# picotouch_grid.net
KiCad netlist of a schematic drawn in EAGLE
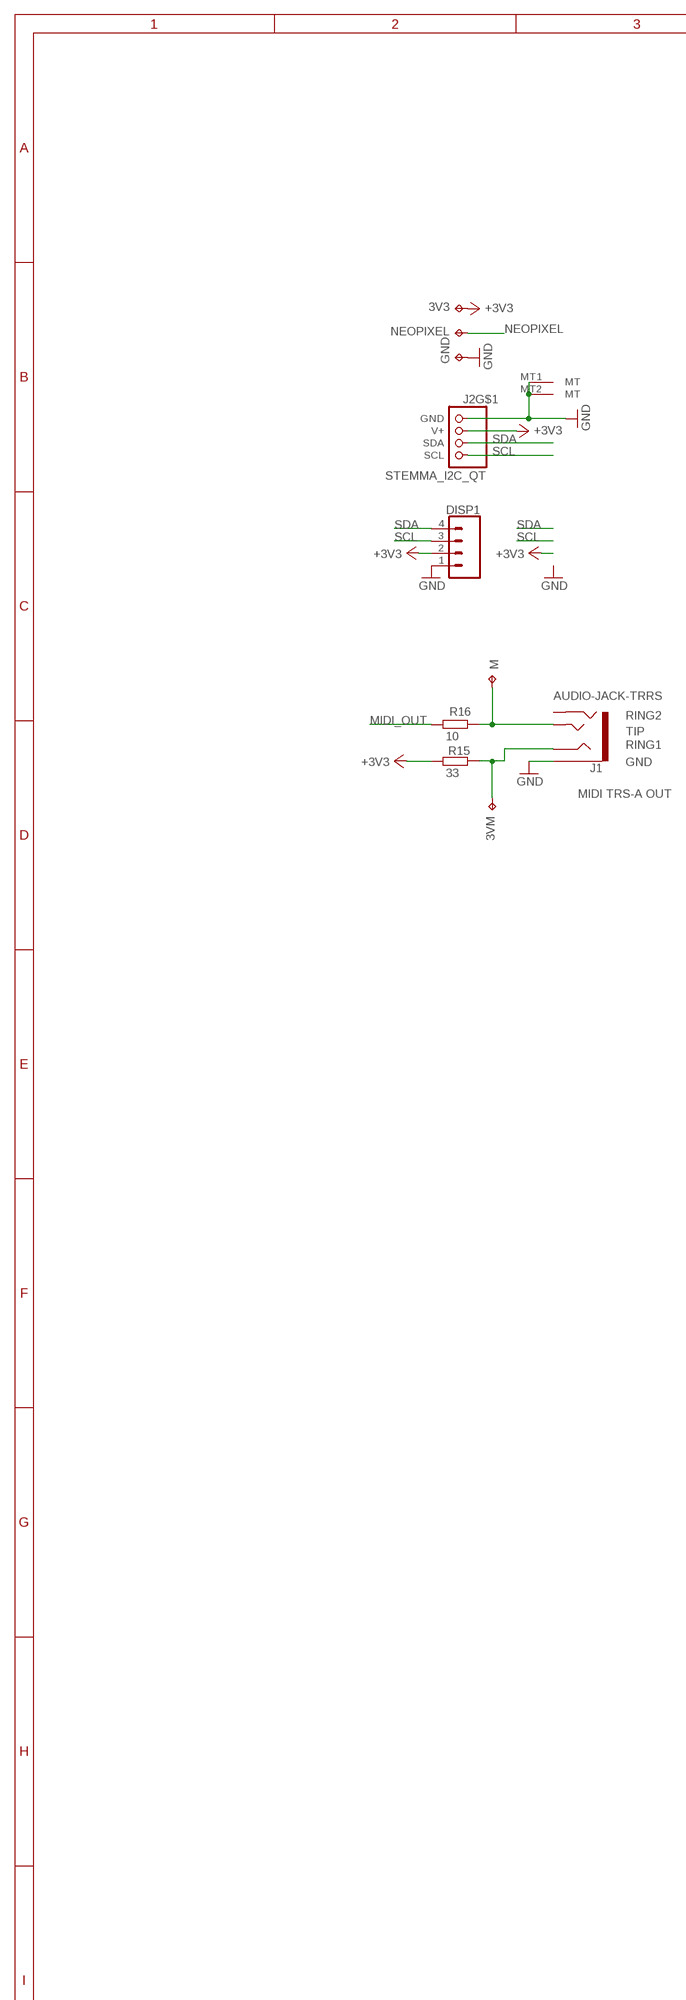
[diagram p0: schematic, sheet 1, part 1 of 2]
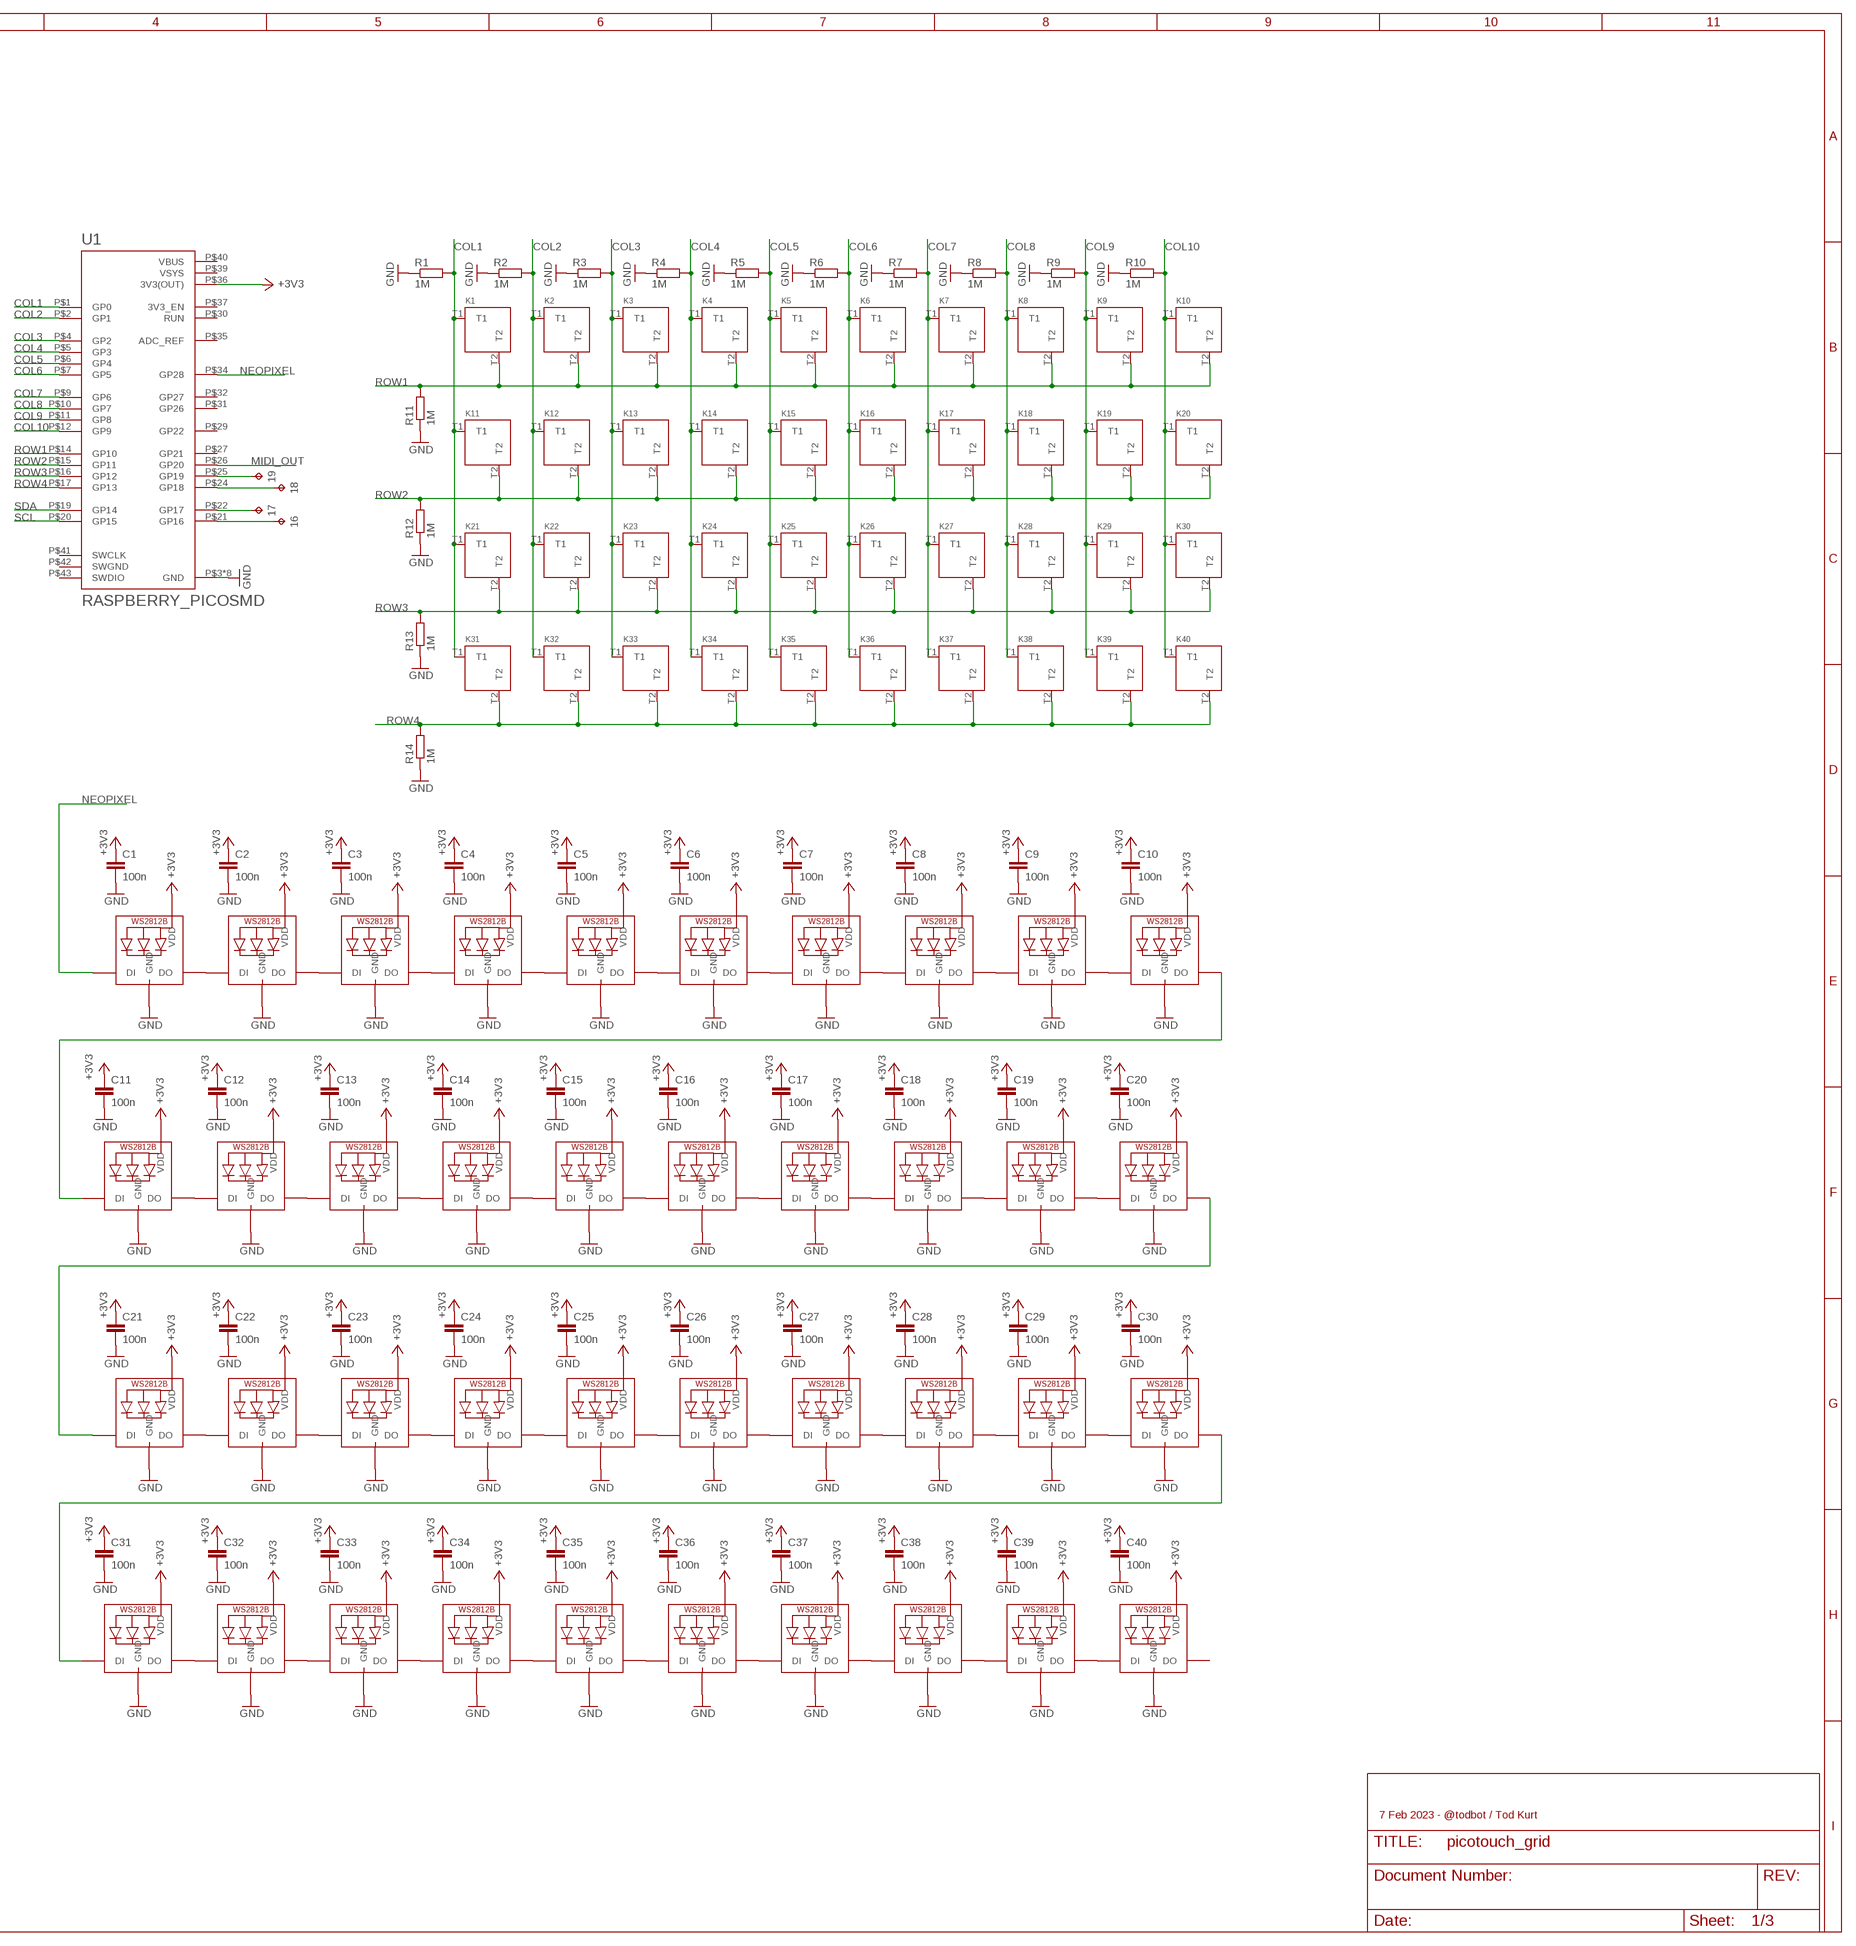
[diagram p1: schematic, sheet 1, part 2 of 2]

(export (version "E")
  (design (tool "Eeschema 10.0.6"))
  (components
    (comp (ref "3V3")
      (value "TPTP15R")
      (footprint "eagle-import:TP15R")
      (libsource (lib "eagle-import") (part "TPTP15R"))
    )
    (comp (ref "3VM")
      (value "TPTP15R")
      (footprint "eagle-import:TP15R")
      (libsource (lib "eagle-import") (part "TPTP15R"))
    )
    (comp (ref "16")
      (value "TPTP15R")
      (footprint "eagle-import:TP15R")
      (libsource (lib "eagle-import") (part "TPTP15R"))
    )
    (comp (ref "17")
      (value "TPTP15R")
      (footprint "eagle-import:TP15R")
      (libsource (lib "eagle-import") (part "TPTP15R"))
    )
    (comp (ref "18")
      (value "TPTP15R")
      (footprint "eagle-import:TP15R")
      (libsource (lib "eagle-import") (part "TPTP15R"))
    )
    (comp (ref "19")
      (value "TPTP15R")
      (footprint "eagle-import:TP15R")
      (libsource (lib "eagle-import") (part "TPTP15R"))
    )
    (comp (ref "C1")
      (value "100n")
      (footprint "eagle-import:C0805")
      (libsource (lib "eagle-import") (part "C-EUC0805"))
    )
    (comp (ref "C2")
      (value "100n")
      (footprint "eagle-import:C0805")
      (libsource (lib "eagle-import") (part "C-EUC0805"))
    )
    (comp (ref "C3")
      (value "100n")
      (footprint "eagle-import:C0805")
      (libsource (lib "eagle-import") (part "C-EUC0805"))
    )
    (comp (ref "C4")
      (value "100n")
      (footprint "eagle-import:C0805")
      (libsource (lib "eagle-import") (part "C-EUC0805"))
    )
    (comp (ref "C5")
      (value "100n")
      (footprint "eagle-import:C0805")
      (libsource (lib "eagle-import") (part "C-EUC0805"))
    )
    (comp (ref "C6")
      (value "100n")
      (footprint "eagle-import:C0805")
      (libsource (lib "eagle-import") (part "C-EUC0805"))
    )
    (comp (ref "C7")
      (value "100n")
      (footprint "eagle-import:C0805")
      (libsource (lib "eagle-import") (part "C-EUC0805"))
    )
    (comp (ref "C8")
      (value "100n")
      (footprint "eagle-import:C0805")
      (libsource (lib "eagle-import") (part "C-EUC0805"))
    )
    (comp (ref "C9")
      (value "100n")
      (footprint "eagle-import:C0805")
      (libsource (lib "eagle-import") (part "C-EUC0805"))
    )
    (comp (ref "C10")
      (value "100n")
      (footprint "eagle-import:C0805")
      (libsource (lib "eagle-import") (part "C-EUC0805"))
    )
    (comp (ref "C11")
      (value "100n")
      (footprint "eagle-import:C0805")
      (libsource (lib "eagle-import") (part "C-EUC0805"))
    )
    (comp (ref "C12")
      (value "100n")
      (footprint "eagle-import:C0805")
      (libsource (lib "eagle-import") (part "C-EUC0805"))
    )
    (comp (ref "C13")
      (value "100n")
      (footprint "eagle-import:C0805")
      (libsource (lib "eagle-import") (part "C-EUC0805"))
    )
    (comp (ref "C14")
      (value "100n")
      (footprint "eagle-import:C0805")
      (libsource (lib "eagle-import") (part "C-EUC0805"))
    )
    (comp (ref "C15")
      (value "100n")
      (footprint "eagle-import:C0805")
      (libsource (lib "eagle-import") (part "C-EUC0805"))
    )
    (comp (ref "C16")
      (value "100n")
      (footprint "eagle-import:C0805")
      (libsource (lib "eagle-import") (part "C-EUC0805"))
    )
    (comp (ref "C17")
      (value "100n")
      (footprint "eagle-import:C0805")
      (libsource (lib "eagle-import") (part "C-EUC0805"))
    )
    (comp (ref "C18")
      (value "100n")
      (footprint "eagle-import:C0805")
      (libsource (lib "eagle-import") (part "C-EUC0805"))
    )
    (comp (ref "C19")
      (value "100n")
      (footprint "eagle-import:C0805")
      (libsource (lib "eagle-import") (part "C-EUC0805"))
    )
    (comp (ref "C20")
      (value "100n")
      (footprint "eagle-import:C0805")
      (libsource (lib "eagle-import") (part "C-EUC0805"))
    )
    (comp (ref "C21")
      (value "100n")
      (footprint "eagle-import:C0805")
      (libsource (lib "eagle-import") (part "C-EUC0805"))
    )
    (comp (ref "C22")
      (value "100n")
      (footprint "eagle-import:C0805")
      (libsource (lib "eagle-import") (part "C-EUC0805"))
    )
    (comp (ref "C23")
      (value "100n")
      (footprint "eagle-import:C0805")
      (libsource (lib "eagle-import") (part "C-EUC0805"))
    )
    (comp (ref "C24")
      (value "100n")
      (footprint "eagle-import:C0805")
      (libsource (lib "eagle-import") (part "C-EUC0805"))
    )
    (comp (ref "C25")
      (value "100n")
      (footprint "eagle-import:C0805")
      (libsource (lib "eagle-import") (part "C-EUC0805"))
    )
    (comp (ref "C26")
      (value "100n")
      (footprint "eagle-import:C0805")
      (libsource (lib "eagle-import") (part "C-EUC0805"))
    )
    (comp (ref "C27")
      (value "100n")
      (footprint "eagle-import:C0805")
      (libsource (lib "eagle-import") (part "C-EUC0805"))
    )
    (comp (ref "C28")
      (value "100n")
      (footprint "eagle-import:C0805")
      (libsource (lib "eagle-import") (part "C-EUC0805"))
    )
    (comp (ref "C29")
      (value "100n")
      (footprint "eagle-import:C0805")
      (libsource (lib "eagle-import") (part "C-EUC0805"))
    )
    (comp (ref "C30")
      (value "100n")
      (footprint "eagle-import:C0805")
      (libsource (lib "eagle-import") (part "C-EUC0805"))
    )
    (comp (ref "C31")
      (value "100n")
      (footprint "eagle-import:C0805")
      (libsource (lib "eagle-import") (part "C-EUC0805"))
    )
    (comp (ref "C32")
      (value "100n")
      (footprint "eagle-import:C0805")
      (libsource (lib "eagle-import") (part "C-EUC0805"))
    )
    (comp (ref "C33")
      (value "100n")
      (footprint "eagle-import:C0805")
      (libsource (lib "eagle-import") (part "C-EUC0805"))
    )
    (comp (ref "C34")
      (value "100n")
      (footprint "eagle-import:C0805")
      (libsource (lib "eagle-import") (part "C-EUC0805"))
    )
    (comp (ref "C35")
      (value "100n")
      (footprint "eagle-import:C0805")
      (libsource (lib "eagle-import") (part "C-EUC0805"))
    )
    (comp (ref "C36")
      (value "100n")
      (footprint "eagle-import:C0805")
      (libsource (lib "eagle-import") (part "C-EUC0805"))
    )
    (comp (ref "C37")
      (value "100n")
      (footprint "eagle-import:C0805")
      (libsource (lib "eagle-import") (part "C-EUC0805"))
    )
    (comp (ref "C38")
      (value "100n")
      (footprint "eagle-import:C0805")
      (libsource (lib "eagle-import") (part "C-EUC0805"))
    )
    (comp (ref "C39")
      (value "100n")
      (footprint "eagle-import:C0805")
      (libsource (lib "eagle-import") (part "C-EUC0805"))
    )
    (comp (ref "C40")
      (value "100n")
      (footprint "eagle-import:C0805")
      (libsource (lib "eagle-import") (part "C-EUC0805"))
    )
    (comp (ref "DISP1")
      (value "CONN_04")
      (footprint "eagle-import:1X04")
      (libsource (lib "eagle-import") (part "CONN_04"))
    )
    (comp (ref "GND")
      (value "TPTP15R")
      (footprint "eagle-import:TP15R")
      (libsource (lib "eagle-import") (part "TPTP15R"))
    )
    (comp (ref "J1")
      (value "AUDIO-JACK-TRRS")
      (footprint "eagle-import:PJ-320D_SPARKFUN")
      (fields (field (name "MPN") "PJ-320D") (field (name "LCSC") "C431535"))
      (libsource (lib "eagle-import") (part "AUDIO-JACK-TRRS"))
    )
    (comp (ref "J2")
      (value "STEMMA_I2C_QT")
      (footprint "eagle-import:JST_SH4")
      (fields
        (field (name "MPN") "HC-1.0-4PWT")
        (field (name "LCSC2") "C160404")
        (field (name "MPN2") "SM04B-SRSS-TB")
      )
      (libsource (lib "eagle-import") (part "STEMMA_I2C_QT"))
    )
    (comp (ref "K1")
      (value "TOUCHKEYH")
      (footprint "eagle-import:TOUCHPAD_KEY_0.5IN_LEDHOLE")
      (libsource (lib "eagle-import") (part "TOUCHKEYH"))
    )
    (comp (ref "K2")
      (value "TOUCHKEYH")
      (footprint "eagle-import:TOUCHPAD_KEY_0.5IN_LEDHOLE")
      (libsource (lib "eagle-import") (part "TOUCHKEYH"))
    )
    (comp (ref "K3")
      (value "TOUCHKEYH")
      (footprint "eagle-import:TOUCHPAD_KEY_0.5IN_LEDHOLE")
      (libsource (lib "eagle-import") (part "TOUCHKEYH"))
    )
    (comp (ref "K4")
      (value "TOUCHKEYH")
      (footprint "eagle-import:TOUCHPAD_KEY_0.5IN_LEDHOLE")
      (libsource (lib "eagle-import") (part "TOUCHKEYH"))
    )
    (comp (ref "K5")
      (value "TOUCHKEYH")
      (footprint "eagle-import:TOUCHPAD_KEY_0.5IN_LEDHOLE")
      (libsource (lib "eagle-import") (part "TOUCHKEYH"))
    )
    (comp (ref "K6")
      (value "TOUCHKEYH")
      (footprint "eagle-import:TOUCHPAD_KEY_0.5IN_LEDHOLE")
      (libsource (lib "eagle-import") (part "TOUCHKEYH"))
    )
    (comp (ref "K7")
      (value "TOUCHKEYH")
      (footprint "eagle-import:TOUCHPAD_KEY_0.5IN_LEDHOLE")
      (libsource (lib "eagle-import") (part "TOUCHKEYH"))
    )
    (comp (ref "K8")
      (value "TOUCHKEYH")
      (footprint "eagle-import:TOUCHPAD_KEY_0.5IN_LEDHOLE")
      (libsource (lib "eagle-import") (part "TOUCHKEYH"))
    )
    (comp (ref "K9")
      (value "TOUCHKEYH")
      (footprint "eagle-import:TOUCHPAD_KEY_0.5IN_LEDHOLE")
      (libsource (lib "eagle-import") (part "TOUCHKEYH"))
    )
    (comp (ref "K10")
      (value "TOUCHKEYH")
      (footprint "eagle-import:TOUCHPAD_KEY_0.5IN_LEDHOLE")
      (libsource (lib "eagle-import") (part "TOUCHKEYH"))
    )
    (comp (ref "K11")
      (value "TOUCHKEYH")
      (footprint "eagle-import:TOUCHPAD_KEY_0.5IN_LEDHOLE")
      (libsource (lib "eagle-import") (part "TOUCHKEYH"))
    )
    (comp (ref "K12")
      (value "TOUCHKEYH")
      (footprint "eagle-import:TOUCHPAD_KEY_0.5IN_LEDHOLE")
      (libsource (lib "eagle-import") (part "TOUCHKEYH"))
    )
    (comp (ref "K13")
      (value "TOUCHKEYH")
      (footprint "eagle-import:TOUCHPAD_KEY_0.5IN_LEDHOLE")
      (libsource (lib "eagle-import") (part "TOUCHKEYH"))
    )
    (comp (ref "K14")
      (value "TOUCHKEYH")
      (footprint "eagle-import:TOUCHPAD_KEY_0.5IN_LEDHOLE")
      (libsource (lib "eagle-import") (part "TOUCHKEYH"))
    )
    (comp (ref "K15")
      (value "TOUCHKEYH")
      (footprint "eagle-import:TOUCHPAD_KEY_0.5IN_LEDHOLE")
      (libsource (lib "eagle-import") (part "TOUCHKEYH"))
    )
    (comp (ref "K16")
      (value "TOUCHKEYH")
      (footprint "eagle-import:TOUCHPAD_KEY_0.5IN_LEDHOLE")
      (libsource (lib "eagle-import") (part "TOUCHKEYH"))
    )
    (comp (ref "K17")
      (value "TOUCHKEYH")
      (footprint "eagle-import:TOUCHPAD_KEY_0.5IN_LEDHOLE")
      (libsource (lib "eagle-import") (part "TOUCHKEYH"))
    )
    (comp (ref "K18")
      (value "TOUCHKEYH")
      (footprint "eagle-import:TOUCHPAD_KEY_0.5IN_LEDHOLE")
      (libsource (lib "eagle-import") (part "TOUCHKEYH"))
    )
    (comp (ref "K19")
      (value "TOUCHKEYH")
      (footprint "eagle-import:TOUCHPAD_KEY_0.5IN_LEDHOLE")
      (libsource (lib "eagle-import") (part "TOUCHKEYH"))
    )
    (comp (ref "K20")
      (value "TOUCHKEYH")
      (footprint "eagle-import:TOUCHPAD_KEY_0.5IN_LEDHOLE")
      (libsource (lib "eagle-import") (part "TOUCHKEYH"))
    )
    (comp (ref "K21")
      (value "TOUCHKEYH")
      (footprint "eagle-import:TOUCHPAD_KEY_0.5IN_LEDHOLE")
      (libsource (lib "eagle-import") (part "TOUCHKEYH"))
    )
    (comp (ref "K22")
      (value "TOUCHKEYH")
      (footprint "eagle-import:TOUCHPAD_KEY_0.5IN_LEDHOLE")
      (libsource (lib "eagle-import") (part "TOUCHKEYH"))
    )
    (comp (ref "K23")
      (value "TOUCHKEYH")
      (footprint "eagle-import:TOUCHPAD_KEY_0.5IN_LEDHOLE")
      (libsource (lib "eagle-import") (part "TOUCHKEYH"))
    )
    (comp (ref "K24")
      (value "TOUCHKEYH")
      (footprint "eagle-import:TOUCHPAD_KEY_0.5IN_LEDHOLE")
      (libsource (lib "eagle-import") (part "TOUCHKEYH"))
    )
    (comp (ref "K25")
      (value "TOUCHKEYH")
      (footprint "eagle-import:TOUCHPAD_KEY_0.5IN_LEDHOLE")
      (libsource (lib "eagle-import") (part "TOUCHKEYH"))
    )
    (comp (ref "K26")
      (value "TOUCHKEYH")
      (footprint "eagle-import:TOUCHPAD_KEY_0.5IN_LEDHOLE")
      (libsource (lib "eagle-import") (part "TOUCHKEYH"))
    )
    (comp (ref "K27")
      (value "TOUCHKEYH")
      (footprint "eagle-import:TOUCHPAD_KEY_0.5IN_LEDHOLE")
      (libsource (lib "eagle-import") (part "TOUCHKEYH"))
    )
    (comp (ref "K28")
      (value "TOUCHKEYH")
      (footprint "eagle-import:TOUCHPAD_KEY_0.5IN_LEDHOLE")
      (libsource (lib "eagle-import") (part "TOUCHKEYH"))
    )
    (comp (ref "K29")
      (value "TOUCHKEYH")
      (footprint "eagle-import:TOUCHPAD_KEY_0.5IN_LEDHOLE")
      (libsource (lib "eagle-import") (part "TOUCHKEYH"))
    )
    (comp (ref "K30")
      (value "TOUCHKEYH")
      (footprint "eagle-import:TOUCHPAD_KEY_0.5IN_LEDHOLE")
      (libsource (lib "eagle-import") (part "TOUCHKEYH"))
    )
    (comp (ref "K31")
      (value "TOUCHKEYH")
      (footprint "eagle-import:TOUCHPAD_KEY_0.5IN_LEDHOLE")
      (libsource (lib "eagle-import") (part "TOUCHKEYH"))
    )
    (comp (ref "K32")
      (value "TOUCHKEYH")
      (footprint "eagle-import:TOUCHPAD_KEY_0.5IN_LEDHOLE")
      (libsource (lib "eagle-import") (part "TOUCHKEYH"))
    )
    (comp (ref "K33")
      (value "TOUCHKEYH")
      (footprint "eagle-import:TOUCHPAD_KEY_0.5IN_LEDHOLE")
      (libsource (lib "eagle-import") (part "TOUCHKEYH"))
    )
    (comp (ref "K34")
      (value "TOUCHKEYH")
      (footprint "eagle-import:TOUCHPAD_KEY_0.5IN_LEDHOLE")
      (libsource (lib "eagle-import") (part "TOUCHKEYH"))
    )
    (comp (ref "K35")
      (value "TOUCHKEYH")
      (footprint "eagle-import:TOUCHPAD_KEY_0.5IN_LEDHOLE")
      (libsource (lib "eagle-import") (part "TOUCHKEYH"))
    )
    (comp (ref "K36")
      (value "TOUCHKEYH")
      (footprint "eagle-import:TOUCHPAD_KEY_0.5IN_LEDHOLE")
      (libsource (lib "eagle-import") (part "TOUCHKEYH"))
    )
    (comp (ref "K37")
      (value "TOUCHKEYH")
      (footprint "eagle-import:TOUCHPAD_KEY_0.5IN_LEDHOLE")
      (libsource (lib "eagle-import") (part "TOUCHKEYH"))
    )
    (comp (ref "K38")
      (value "TOUCHKEYH")
      (footprint "eagle-import:TOUCHPAD_KEY_0.5IN_LEDHOLE")
      (libsource (lib "eagle-import") (part "TOUCHKEYH"))
    )
    (comp (ref "K39")
      (value "TOUCHKEYH")
      (footprint "eagle-import:TOUCHPAD_KEY_0.5IN_LEDHOLE")
      (libsource (lib "eagle-import") (part "TOUCHKEYH"))
    )
    (comp (ref "K40")
      (value "TOUCHKEYH")
      (footprint "eagle-import:TOUCHPAD_KEY_0.5IN_LEDHOLE")
      (libsource (lib "eagle-import") (part "TOUCHKEYH"))
    )
    (comp (ref "LED1")
      (value "MICROBUILDER_WS2812B_SK6812E")
      (footprint "eagle-import:MICROBUILDER_NEO3535_REVERSE")
      (libsource (lib "eagle-import") (part "MICROBUILDER_WS2812B_SK6812E"))
    )
    (comp (ref "LED2")
      (value "MICROBUILDER_WS2812B_SK6812E")
      (footprint "eagle-import:MICROBUILDER_NEO3535_REVERSE")
      (libsource (lib "eagle-import") (part "MICROBUILDER_WS2812B_SK6812E"))
    )
    (comp (ref "LED3")
      (value "MICROBUILDER_WS2812B_SK6812E")
      (footprint "eagle-import:MICROBUILDER_NEO3535_REVERSE")
      (libsource (lib "eagle-import") (part "MICROBUILDER_WS2812B_SK6812E"))
    )
    (comp (ref "LED4")
      (value "MICROBUILDER_WS2812B_SK6812E")
      (footprint "eagle-import:MICROBUILDER_NEO3535_REVERSE")
      (libsource (lib "eagle-import") (part "MICROBUILDER_WS2812B_SK6812E"))
    )
    (comp (ref "LED5")
      (value "MICROBUILDER_WS2812B_SK6812E")
      (footprint "eagle-import:MICROBUILDER_NEO3535_REVERSE")
      (libsource (lib "eagle-import") (part "MICROBUILDER_WS2812B_SK6812E"))
    )
    (comp (ref "LED6")
      (value "MICROBUILDER_WS2812B_SK6812E")
      (footprint "eagle-import:MICROBUILDER_NEO3535_REVERSE")
      (libsource (lib "eagle-import") (part "MICROBUILDER_WS2812B_SK6812E"))
    )
    (comp (ref "LED7")
      (value "MICROBUILDER_WS2812B_SK6812E")
      (footprint "eagle-import:MICROBUILDER_NEO3535_REVERSE")
      (libsource (lib "eagle-import") (part "MICROBUILDER_WS2812B_SK6812E"))
    )
    (comp (ref "LED8")
      (value "MICROBUILDER_WS2812B_SK6812E")
      (footprint "eagle-import:MICROBUILDER_NEO3535_REVERSE")
      (libsource (lib "eagle-import") (part "MICROBUILDER_WS2812B_SK6812E"))
    )
    (comp (ref "LED9")
      (value "MICROBUILDER_WS2812B_SK6812E")
      (footprint "eagle-import:MICROBUILDER_NEO3535_REVERSE")
      (libsource (lib "eagle-import") (part "MICROBUILDER_WS2812B_SK6812E"))
    )
    (comp (ref "LED10")
      (value "MICROBUILDER_WS2812B_SK6812E")
      (footprint "eagle-import:MICROBUILDER_NEO3535_REVERSE")
      (libsource (lib "eagle-import") (part "MICROBUILDER_WS2812B_SK6812E"))
    )
    (comp (ref "LED11")
      (value "MICROBUILDER_WS2812B_SK6812E")
      (footprint "eagle-import:MICROBUILDER_NEO3535_REVERSE")
      (libsource (lib "eagle-import") (part "MICROBUILDER_WS2812B_SK6812E"))
    )
    (comp (ref "LED12")
      (value "MICROBUILDER_WS2812B_SK6812E")
      (footprint "eagle-import:MICROBUILDER_NEO3535_REVERSE")
      (libsource (lib "eagle-import") (part "MICROBUILDER_WS2812B_SK6812E"))
    )
    (comp (ref "LED13")
      (value "MICROBUILDER_WS2812B_SK6812E")
      (footprint "eagle-import:MICROBUILDER_NEO3535_REVERSE")
      (libsource (lib "eagle-import") (part "MICROBUILDER_WS2812B_SK6812E"))
    )
    (comp (ref "LED14")
      (value "MICROBUILDER_WS2812B_SK6812E")
      (footprint "eagle-import:MICROBUILDER_NEO3535_REVERSE")
      (libsource (lib "eagle-import") (part "MICROBUILDER_WS2812B_SK6812E"))
    )
    (comp (ref "LED15")
      (value "MICROBUILDER_WS2812B_SK6812E")
      (footprint "eagle-import:MICROBUILDER_NEO3535_REVERSE")
      (libsource (lib "eagle-import") (part "MICROBUILDER_WS2812B_SK6812E"))
    )
    (comp (ref "LED16")
      (value "MICROBUILDER_WS2812B_SK6812E")
      (footprint "eagle-import:MICROBUILDER_NEO3535_REVERSE")
      (libsource (lib "eagle-import") (part "MICROBUILDER_WS2812B_SK6812E"))
    )
    (comp (ref "LED17")
      (value "MICROBUILDER_WS2812B_SK6812E")
      (footprint "eagle-import:MICROBUILDER_NEO3535_REVERSE")
      (libsource (lib "eagle-import") (part "MICROBUILDER_WS2812B_SK6812E"))
    )
    (comp (ref "LED18")
      (value "MICROBUILDER_WS2812B_SK6812E")
      (footprint "eagle-import:MICROBUILDER_NEO3535_REVERSE")
      (libsource (lib "eagle-import") (part "MICROBUILDER_WS2812B_SK6812E"))
    )
    (comp (ref "LED19")
      (value "MICROBUILDER_WS2812B_SK6812E")
      (footprint "eagle-import:MICROBUILDER_NEO3535_REVERSE")
      (libsource (lib "eagle-import") (part "MICROBUILDER_WS2812B_SK6812E"))
    )
    (comp (ref "LED20")
      (value "MICROBUILDER_WS2812B_SK6812E")
      (footprint "eagle-import:MICROBUILDER_NEO3535_REVERSE")
      (libsource (lib "eagle-import") (part "MICROBUILDER_WS2812B_SK6812E"))
    )
    (comp (ref "LED21")
      (value "MICROBUILDER_WS2812B_SK6812E")
      (footprint "eagle-import:MICROBUILDER_NEO3535_REVERSE")
      (libsource (lib "eagle-import") (part "MICROBUILDER_WS2812B_SK6812E"))
    )
    (comp (ref "LED22")
      (value "MICROBUILDER_WS2812B_SK6812E")
      (footprint "eagle-import:MICROBUILDER_NEO3535_REVERSE")
      (libsource (lib "eagle-import") (part "MICROBUILDER_WS2812B_SK6812E"))
    )
    (comp (ref "LED23")
      (value "MICROBUILDER_WS2812B_SK6812E")
      (footprint "eagle-import:MICROBUILDER_NEO3535_REVERSE")
      (libsource (lib "eagle-import") (part "MICROBUILDER_WS2812B_SK6812E"))
    )
    (comp (ref "LED24")
      (value "MICROBUILDER_WS2812B_SK6812E")
      (footprint "eagle-import:MICROBUILDER_NEO3535_REVERSE")
      (libsource (lib "eagle-import") (part "MICROBUILDER_WS2812B_SK6812E"))
    )
    (comp (ref "LED25")
      (value "MICROBUILDER_WS2812B_SK6812E")
      (footprint "eagle-import:MICROBUILDER_NEO3535_REVERSE")
      (libsource (lib "eagle-import") (part "MICROBUILDER_WS2812B_SK6812E"))
    )
    (comp (ref "LED26")
      (value "MICROBUILDER_WS2812B_SK6812E")
      (footprint "eagle-import:MICROBUILDER_NEO3535_REVERSE")
      (libsource (lib "eagle-import") (part "MICROBUILDER_WS2812B_SK6812E"))
    )
    (comp (ref "LED27")
      (value "MICROBUILDER_WS2812B_SK6812E")
      (footprint "eagle-import:MICROBUILDER_NEO3535_REVERSE")
      (libsource (lib "eagle-import") (part "MICROBUILDER_WS2812B_SK6812E"))
    )
    (comp (ref "LED28")
      (value "MICROBUILDER_WS2812B_SK6812E")
      (footprint "eagle-import:MICROBUILDER_NEO3535_REVERSE")
      (libsource (lib "eagle-import") (part "MICROBUILDER_WS2812B_SK6812E"))
    )
    (comp (ref "LED29")
      (value "MICROBUILDER_WS2812B_SK6812E")
      (footprint "eagle-import:MICROBUILDER_NEO3535_REVERSE")
      (libsource (lib "eagle-import") (part "MICROBUILDER_WS2812B_SK6812E"))
    )
    (comp (ref "LED30")
      (value "MICROBUILDER_WS2812B_SK6812E")
      (footprint "eagle-import:MICROBUILDER_NEO3535_REVERSE")
      (libsource (lib "eagle-import") (part "MICROBUILDER_WS2812B_SK6812E"))
    )
    (comp (ref "LED31")
      (value "MICROBUILDER_WS2812B_SK6812E")
      (footprint "eagle-import:MICROBUILDER_NEO3535_REVERSE")
      (libsource (lib "eagle-import") (part "MICROBUILDER_WS2812B_SK6812E"))
    )
    (comp (ref "LED32")
      (value "MICROBUILDER_WS2812B_SK6812E")
      (footprint "eagle-import:MICROBUILDER_NEO3535_REVERSE")
      (libsource (lib "eagle-import") (part "MICROBUILDER_WS2812B_SK6812E"))
    )
    (comp (ref "LED33")
      (value "MICROBUILDER_WS2812B_SK6812E")
      (footprint "eagle-import:MICROBUILDER_NEO3535_REVERSE")
      (libsource (lib "eagle-import") (part "MICROBUILDER_WS2812B_SK6812E"))
    )
    (comp (ref "LED34")
      (value "MICROBUILDER_WS2812B_SK6812E")
      (footprint "eagle-import:MICROBUILDER_NEO3535_REVERSE")
      (libsource (lib "eagle-import") (part "MICROBUILDER_WS2812B_SK6812E"))
    )
    (comp (ref "LED35")
      (value "MICROBUILDER_WS2812B_SK6812E")
      (footprint "eagle-import:MICROBUILDER_NEO3535_REVERSE")
      (libsource (lib "eagle-import") (part "MICROBUILDER_WS2812B_SK6812E"))
    )
    (comp (ref "LED36")
      (value "MICROBUILDER_WS2812B_SK6812E")
      (footprint "eagle-import:MICROBUILDER_NEO3535_REVERSE")
      (libsource (lib "eagle-import") (part "MICROBUILDER_WS2812B_SK6812E"))
    )
    (comp (ref "LED37")
      (value "MICROBUILDER_WS2812B_SK6812E")
      (footprint "eagle-import:MICROBUILDER_NEO3535_REVERSE")
      (libsource (lib "eagle-import") (part "MICROBUILDER_WS2812B_SK6812E"))
    )
    (comp (ref "LED38")
      (value "MICROBUILDER_WS2812B_SK6812E")
      (footprint "eagle-import:MICROBUILDER_NEO3535_REVERSE")
      (libsource (lib "eagle-import") (part "MICROBUILDER_WS2812B_SK6812E"))
    )
    (comp (ref "LED39")
      (value "MICROBUILDER_WS2812B_SK6812E")
      (footprint "eagle-import:MICROBUILDER_NEO3535_REVERSE")
      (libsource (lib "eagle-import") (part "MICROBUILDER_WS2812B_SK6812E"))
    )
    (comp (ref "LED40")
      (value "MICROBUILDER_WS2812B_SK6812E")
      (footprint "eagle-import:MICROBUILDER_NEO3535_REVERSE")
      (libsource (lib "eagle-import") (part "MICROBUILDER_WS2812B_SK6812E"))
    )
    (comp (ref "M")
      (value "TPTP15R")
      (footprint "eagle-import:TP15R")
      (libsource (lib "eagle-import") (part "TPTP15R"))
    )
    (comp (ref "NEOPIXEL")
      (value "TPTP15R")
      (footprint "eagle-import:TP15R")
      (libsource (lib "eagle-import") (part "TPTP15R"))
    )
    (comp (ref "R1")
      (value "1M")
      (footprint "eagle-import:R0805")
      (libsource (lib "eagle-import") (part "R-EU_R0805"))
    )
    (comp (ref "R2")
      (value "1M")
      (footprint "eagle-import:R0805")
      (libsource (lib "eagle-import") (part "R-EU_R0805"))
    )
    (comp (ref "R3")
      (value "1M")
      (footprint "eagle-import:R0805")
      (libsource (lib "eagle-import") (part "R-EU_R0805"))
    )
    (comp (ref "R4")
      (value "1M")
      (footprint "eagle-import:R0805")
      (libsource (lib "eagle-import") (part "R-EU_R0805"))
    )
    (comp (ref "R5")
      (value "1M")
      (footprint "eagle-import:R0805")
      (libsource (lib "eagle-import") (part "R-EU_R0805"))
    )
    (comp (ref "R6")
      (value "1M")
      (footprint "eagle-import:R0805")
      (libsource (lib "eagle-import") (part "R-EU_R0805"))
    )
    (comp (ref "R7")
      (value "1M")
      (footprint "eagle-import:R0805")
      (libsource (lib "eagle-import") (part "R-EU_R0805"))
    )
    (comp (ref "R8")
      (value "1M")
      (footprint "eagle-import:R0805")
      (libsource (lib "eagle-import") (part "R-EU_R0805"))
    )
    (comp (ref "R9")
      (value "1M")
      (footprint "eagle-import:R0805")
      (libsource (lib "eagle-import") (part "R-EU_R0805"))
    )
    (comp (ref "R10")
      (value "1M")
      (footprint "eagle-import:R0805")
      (libsource (lib "eagle-import") (part "R-EU_R0805"))
    )
    (comp (ref "R11")
      (value "1M")
      (footprint "eagle-import:R0805")
      (libsource (lib "eagle-import") (part "R-EU_R0805"))
    )
    (comp (ref "R12")
      (value "1M")
      (footprint "eagle-import:R0805")
      (libsource (lib "eagle-import") (part "R-EU_R0805"))
    )
    (comp (ref "R13")
      (value "1M")
      (footprint "eagle-import:R0805")
      (libsource (lib "eagle-import") (part "R-EU_R0805"))
    )
    (comp (ref "R14")
      (value "1M")
      (footprint "eagle-import:R0805")
      (libsource (lib "eagle-import") (part "R-EU_R0805"))
    )
    (comp (ref "R15")
      (value "33")
      (footprint "eagle-import:R0805")
      (libsource (lib "eagle-import") (part "R-EU_R0805"))
    )
    (comp (ref "R16")
      (value "10")
      (footprint "eagle-import:R0805")
      (libsource (lib "eagle-import") (part "R-EU_R0805"))
    )
    (comp (ref "U1")
      (value "RASPBERRY_PICOSMD")
      (footprint "eagle-import:PICO-PKG-SMD")
      (libsource (lib "eagle-import") (part "RASPBERRY_PICOSMD"))
    )
  )
  (nets
    (net (code "1") (name "+3V3") (class "Default")
      (node (ref "3V3") (pin "TP") (pinfunction "TP_TP") (pintype "input"))
      (node (ref "C1") (pin "1") (pinfunction "1_1") (pintype "passive"))
      (node (ref "C10") (pin "1") (pinfunction "1_1") (pintype "passive"))
      (node (ref "C11") (pin "1") (pinfunction "1_1") (pintype "passive"))
      (node (ref "C12") (pin "1") (pinfunction "1_1") (pintype "passive"))
      (node (ref "C13") (pin "1") (pinfunction "1_1") (pintype "passive"))
      (node (ref "C14") (pin "1") (pinfunction "1_1") (pintype "passive"))
      (node (ref "C15") (pin "1") (pinfunction "1_1") (pintype "passive"))
      (node (ref "C16") (pin "1") (pinfunction "1_1") (pintype "passive"))
      (node (ref "C17") (pin "1") (pinfunction "1_1") (pintype "passive"))
      (node (ref "C18") (pin "1") (pinfunction "1_1") (pintype "passive"))
      (node (ref "C19") (pin "1") (pinfunction "1_1") (pintype "passive"))
      (node (ref "C2") (pin "1") (pinfunction "1_1") (pintype "passive"))
      (node (ref "C20") (pin "1") (pinfunction "1_1") (pintype "passive"))
      (node (ref "C21") (pin "1") (pinfunction "1_1") (pintype "passive"))
      (node (ref "C22") (pin "1") (pinfunction "1_1") (pintype "passive"))
      (node (ref "C23") (pin "1") (pinfunction "1_1") (pintype "passive"))
      (node (ref "C24") (pin "1") (pinfunction "1_1") (pintype "passive"))
      (node (ref "C25") (pin "1") (pinfunction "1_1") (pintype "passive"))
      (node (ref "C26") (pin "1") (pinfunction "1_1") (pintype "passive"))
      (node (ref "C27") (pin "1") (pinfunction "1_1") (pintype "passive"))
      (node (ref "C28") (pin "1") (pinfunction "1_1") (pintype "passive"))
      (node (ref "C29") (pin "1") (pinfunction "1_1") (pintype "passive"))
      (node (ref "C3") (pin "1") (pinfunction "1_1") (pintype "passive"))
      (node (ref "C30") (pin "1") (pinfunction "1_1") (pintype "passive"))
      (node (ref "C31") (pin "1") (pinfunction "1_1") (pintype "passive"))
      (node (ref "C32") (pin "1") (pinfunction "1_1") (pintype "passive"))
      (node (ref "C33") (pin "1") (pinfunction "1_1") (pintype "passive"))
      (node (ref "C34") (pin "1") (pinfunction "1_1") (pintype "passive"))
      (node (ref "C35") (pin "1") (pinfunction "1_1") (pintype "passive"))
      (node (ref "C36") (pin "1") (pinfunction "1_1") (pintype "passive"))
      (node (ref "C37") (pin "1") (pinfunction "1_1") (pintype "passive"))
      (node (ref "C38") (pin "1") (pinfunction "1_1") (pintype "passive"))
      (node (ref "C39") (pin "1") (pinfunction "1_1") (pintype "passive"))
      (node (ref "C4") (pin "1") (pinfunction "1_1") (pintype "passive"))
      (node (ref "C40") (pin "1") (pinfunction "1_1") (pintype "passive"))
      (node (ref "C5") (pin "1") (pinfunction "1_1") (pintype "passive"))
      (node (ref "C6") (pin "1") (pinfunction "1_1") (pintype "passive"))
      (node (ref "C7") (pin "1") (pinfunction "1_1") (pintype "passive"))
      (node (ref "C8") (pin "1") (pinfunction "1_1") (pintype "passive"))
      (node (ref "C9") (pin "1") (pinfunction "1_1") (pintype "passive"))
      (node (ref "DISP1") (pin "2") (pinfunction "2_2") (pintype "passive"))
      (node (ref "J2") (pin "2") (pinfunction "V+_2") (pintype "passive"))
      (node (ref "LED1") (pin "1-VDD") (pinfunction "VDD_1-VDD") (pintype "power_in"))
      (node (ref "LED10") (pin "1-VDD") (pinfunction "VDD_1-VDD") (pintype "power_in"))
      (node (ref "LED11") (pin "1-VDD") (pinfunction "VDD_1-VDD") (pintype "power_in"))
      (node (ref "LED12") (pin "1-VDD") (pinfunction "VDD_1-VDD") (pintype "power_in"))
      (node (ref "LED13") (pin "1-VDD") (pinfunction "VDD_1-VDD") (pintype "power_in"))
      (node (ref "LED14") (pin "1-VDD") (pinfunction "VDD_1-VDD") (pintype "power_in"))
      (node (ref "LED15") (pin "1-VDD") (pinfunction "VDD_1-VDD") (pintype "power_in"))
      (node (ref "LED16") (pin "1-VDD") (pinfunction "VDD_1-VDD") (pintype "power_in"))
      (node (ref "LED17") (pin "1-VDD") (pinfunction "VDD_1-VDD") (pintype "power_in"))
      (node (ref "LED18") (pin "1-VDD") (pinfunction "VDD_1-VDD") (pintype "power_in"))
      (node (ref "LED19") (pin "1-VDD") (pinfunction "VDD_1-VDD") (pintype "power_in"))
      (node (ref "LED2") (pin "1-VDD") (pinfunction "VDD_1-VDD") (pintype "power_in"))
      (node (ref "LED20") (pin "1-VDD") (pinfunction "VDD_1-VDD") (pintype "power_in"))
      (node (ref "LED21") (pin "1-VDD") (pinfunction "VDD_1-VDD") (pintype "power_in"))
      (node (ref "LED22") (pin "1-VDD") (pinfunction "VDD_1-VDD") (pintype "power_in"))
      (node (ref "LED23") (pin "1-VDD") (pinfunction "VDD_1-VDD") (pintype "power_in"))
      (node (ref "LED24") (pin "1-VDD") (pinfunction "VDD_1-VDD") (pintype "power_in"))
      (node (ref "LED25") (pin "1-VDD") (pinfunction "VDD_1-VDD") (pintype "power_in"))
      (node (ref "LED26") (pin "1-VDD") (pinfunction "VDD_1-VDD") (pintype "power_in"))
      (node (ref "LED27") (pin "1-VDD") (pinfunction "VDD_1-VDD") (pintype "power_in"))
      (node (ref "LED28") (pin "1-VDD") (pinfunction "VDD_1-VDD") (pintype "power_in"))
      (node (ref "LED29") (pin "1-VDD") (pinfunction "VDD_1-VDD") (pintype "power_in"))
      (node (ref "LED3") (pin "1-VDD") (pinfunction "VDD_1-VDD") (pintype "power_in"))
      (node (ref "LED30") (pin "1-VDD") (pinfunction "VDD_1-VDD") (pintype "power_in"))
      (node (ref "LED31") (pin "1-VDD") (pinfunction "VDD_1-VDD") (pintype "power_in"))
      (node (ref "LED32") (pin "1-VDD") (pinfunction "VDD_1-VDD") (pintype "power_in"))
      (node (ref "LED33") (pin "1-VDD") (pinfunction "VDD_1-VDD") (pintype "power_in"))
      (node (ref "LED34") (pin "1-VDD") (pinfunction "VDD_1-VDD") (pintype "power_in"))
      (node (ref "LED35") (pin "1-VDD") (pinfunction "VDD_1-VDD") (pintype "power_in"))
      (node (ref "LED36") (pin "1-VDD") (pinfunction "VDD_1-VDD") (pintype "power_in"))
      (node (ref "LED37") (pin "1-VDD") (pinfunction "VDD_1-VDD") (pintype "power_in"))
      (node (ref "LED38") (pin "1-VDD") (pinfunction "VDD_1-VDD") (pintype "power_in"))
      (node (ref "LED39") (pin "1-VDD") (pinfunction "VDD_1-VDD") (pintype "power_in"))
      (node (ref "LED4") (pin "1-VDD") (pinfunction "VDD_1-VDD") (pintype "power_in"))
      (node (ref "LED40") (pin "1-VDD") (pinfunction "VDD_1-VDD") (pintype "power_in"))
      (node (ref "LED5") (pin "1-VDD") (pinfunction "VDD_1-VDD") (pintype "power_in"))
      (node (ref "LED6") (pin "1-VDD") (pinfunction "VDD_1-VDD") (pintype "power_in"))
      (node (ref "LED7") (pin "1-VDD") (pinfunction "VDD_1-VDD") (pintype "power_in"))
      (node (ref "LED8") (pin "1-VDD") (pinfunction "VDD_1-VDD") (pintype "power_in"))
      (node (ref "LED9") (pin "1-VDD") (pinfunction "VDD_1-VDD") (pintype "power_in"))
      (node (ref "R15") (pin "2") (pinfunction "2_2") (pintype "passive"))
      (node (ref "U1") (pin "P$36") (pinfunction "3V3(OUT)_P$36") (pintype "power_in"))
    )
    (net (code "2") (name "COL1") (class "Default")
      (node (ref "K1") (pin "T1") (pinfunction "T1_T1") (pintype "bidirectional"))
      (node (ref "K11") (pin "T1") (pinfunction "T1_T1") (pintype "bidirectional"))
      (node (ref "K21") (pin "T1") (pinfunction "T1_T1") (pintype "bidirectional"))
      (node (ref "K31") (pin "T1") (pinfunction "T1_T1") (pintype "bidirectional"))
      (node (ref "R1") (pin "2") (pinfunction "2_2") (pintype "passive"))
      (node (ref "U1") (pin "P$1") (pinfunction "GP0_P$1") (pintype "bidirectional"))
    )
    (net (code "3") (name "COL2") (class "Default")
      (node (ref "K12") (pin "T1") (pinfunction "T1_T1") (pintype "bidirectional"))
      (node (ref "K2") (pin "T1") (pinfunction "T1_T1") (pintype "bidirectional"))
      (node (ref "K22") (pin "T1") (pinfunction "T1_T1") (pintype "bidirectional"))
      (node (ref "K32") (pin "T1") (pinfunction "T1_T1") (pintype "bidirectional"))
      (node (ref "R2") (pin "2") (pinfunction "2_2") (pintype "passive"))
      (node (ref "U1") (pin "P$2") (pinfunction "GP1_P$2") (pintype "bidirectional"))
    )
    (net (code "4") (name "COL3") (class "Default")
      (node (ref "K13") (pin "T1") (pinfunction "T1_T1") (pintype "bidirectional"))
      (node (ref "K23") (pin "T1") (pinfunction "T1_T1") (pintype "bidirectional"))
      (node (ref "K3") (pin "T1") (pinfunction "T1_T1") (pintype "bidirectional"))
      (node (ref "K33") (pin "T1") (pinfunction "T1_T1") (pintype "bidirectional"))
      (node (ref "R3") (pin "2") (pinfunction "2_2") (pintype "passive"))
      (node (ref "U1") (pin "P$4") (pinfunction "GP2_P$4") (pintype "bidirectional"))
    )
    (net (code "5") (name "COL4") (class "Default")
      (node (ref "K14") (pin "T1") (pinfunction "T1_T1") (pintype "bidirectional"))
      (node (ref "K24") (pin "T1") (pinfunction "T1_T1") (pintype "bidirectional"))
      (node (ref "K34") (pin "T1") (pinfunction "T1_T1") (pintype "bidirectional"))
      (node (ref "K4") (pin "T1") (pinfunction "T1_T1") (pintype "bidirectional"))
      (node (ref "R4") (pin "2") (pinfunction "2_2") (pintype "passive"))
      (node (ref "U1") (pin "P$5") (pinfunction "GP3_P$5") (pintype "bidirectional"))
    )
    (net (code "6") (name "COL5") (class "Default")
      (node (ref "K15") (pin "T1") (pinfunction "T1_T1") (pintype "bidirectional"))
      (node (ref "K25") (pin "T1") (pinfunction "T1_T1") (pintype "bidirectional"))
      (node (ref "K35") (pin "T1") (pinfunction "T1_T1") (pintype "bidirectional"))
      (node (ref "K5") (pin "T1") (pinfunction "T1_T1") (pintype "bidirectional"))
      (node (ref "R5") (pin "2") (pinfunction "2_2") (pintype "passive"))
      (node (ref "U1") (pin "P$6") (pinfunction "GP4_P$6") (pintype "bidirectional"))
    )
    (net (code "7") (name "COL6") (class "Default")
      (node (ref "K16") (pin "T1") (pinfunction "T1_T1") (pintype "bidirectional"))
      (node (ref "K26") (pin "T1") (pinfunction "T1_T1") (pintype "bidirectional"))
      (node (ref "K36") (pin "T1") (pinfunction "T1_T1") (pintype "bidirectional"))
      (node (ref "K6") (pin "T1") (pinfunction "T1_T1") (pintype "bidirectional"))
      (node (ref "R6") (pin "2") (pinfunction "2_2") (pintype "passive"))
      (node (ref "U1") (pin "P$7") (pinfunction "GP5_P$7") (pintype "bidirectional"))
    )
    (net (code "8") (name "COL7") (class "Default")
      (node (ref "K17") (pin "T1") (pinfunction "T1_T1") (pintype "bidirectional"))
      (node (ref "K27") (pin "T1") (pinfunction "T1_T1") (pintype "bidirectional"))
      (node (ref "K37") (pin "T1") (pinfunction "T1_T1") (pintype "bidirectional"))
      (node (ref "K7") (pin "T1") (pinfunction "T1_T1") (pintype "bidirectional"))
      (node (ref "R7") (pin "2") (pinfunction "2_2") (pintype "passive"))
      (node (ref "U1") (pin "P$9") (pinfunction "GP6_P$9") (pintype "bidirectional"))
    )
    (net (code "9") (name "COL8") (class "Default")
      (node (ref "K18") (pin "T1") (pinfunction "T1_T1") (pintype "bidirectional"))
      (node (ref "K28") (pin "T1") (pinfunction "T1_T1") (pintype "bidirectional"))
      (node (ref "K38") (pin "T1") (pinfunction "T1_T1") (pintype "bidirectional"))
      (node (ref "K8") (pin "T1") (pinfunction "T1_T1") (pintype "bidirectional"))
      (node (ref "R8") (pin "2") (pinfunction "2_2") (pintype "passive"))
      (node (ref "U1") (pin "P$10") (pinfunction "GP7_P$10") (pintype "bidirectional"))
    )
    (net (code "10") (name "COL9") (class "Default")
      (node (ref "K19") (pin "T1") (pinfunction "T1_T1") (pintype "bidirectional"))
      (node (ref "K29") (pin "T1") (pinfunction "T1_T1") (pintype "bidirectional"))
      (node (ref "K39") (pin "T1") (pinfunction "T1_T1") (pintype "bidirectional"))
      (node (ref "K9") (pin "T1") (pinfunction "T1_T1") (pintype "bidirectional"))
      (node (ref "R9") (pin "2") (pinfunction "2_2") (pintype "passive"))
      (node (ref "U1") (pin "P$11") (pinfunction "GP8_P$11") (pintype "bidirectional"))
    )
    (net (code "11") (name "COL10") (class "Default")
      (node (ref "K10") (pin "T1") (pinfunction "T1_T1") (pintype "bidirectional"))
      (node (ref "K20") (pin "T1") (pinfunction "T1_T1") (pintype "bidirectional"))
      (node (ref "K30") (pin "T1") (pinfunction "T1_T1") (pintype "bidirectional"))
      (node (ref "K40") (pin "T1") (pinfunction "T1_T1") (pintype "bidirectional"))
      (node (ref "R10") (pin "2") (pinfunction "2_2") (pintype "passive"))
      (node (ref "U1") (pin "P$12") (pinfunction "GP9_P$12") (pintype "bidirectional"))
    )
    (net (code "12") (name "GND") (class "Default")
      (node (ref "C1") (pin "2") (pinfunction "2_2") (pintype "passive"))
      (node (ref "C10") (pin "2") (pinfunction "2_2") (pintype "passive"))
      (node (ref "C11") (pin "2") (pinfunction "2_2") (pintype "passive"))
      (node (ref "C12") (pin "2") (pinfunction "2_2") (pintype "passive"))
      (node (ref "C13") (pin "2") (pinfunction "2_2") (pintype "passive"))
      (node (ref "C14") (pin "2") (pinfunction "2_2") (pintype "passive"))
      (node (ref "C15") (pin "2") (pinfunction "2_2") (pintype "passive"))
      (node (ref "C16") (pin "2") (pinfunction "2_2") (pintype "passive"))
      (node (ref "C17") (pin "2") (pinfunction "2_2") (pintype "passive"))
      (node (ref "C18") (pin "2") (pinfunction "2_2") (pintype "passive"))
      (node (ref "C19") (pin "2") (pinfunction "2_2") (pintype "passive"))
      (node (ref "C2") (pin "2") (pinfunction "2_2") (pintype "passive"))
      (node (ref "C20") (pin "2") (pinfunction "2_2") (pintype "passive"))
      (node (ref "C21") (pin "2") (pinfunction "2_2") (pintype "passive"))
      (node (ref "C22") (pin "2") (pinfunction "2_2") (pintype "passive"))
      (node (ref "C23") (pin "2") (pinfunction "2_2") (pintype "passive"))
      (node (ref "C24") (pin "2") (pinfunction "2_2") (pintype "passive"))
      (node (ref "C25") (pin "2") (pinfunction "2_2") (pintype "passive"))
      (node (ref "C26") (pin "2") (pinfunction "2_2") (pintype "passive"))
      (node (ref "C27") (pin "2") (pinfunction "2_2") (pintype "passive"))
      (node (ref "C28") (pin "2") (pinfunction "2_2") (pintype "passive"))
      (node (ref "C29") (pin "2") (pinfunction "2_2") (pintype "passive"))
      (node (ref "C3") (pin "2") (pinfunction "2_2") (pintype "passive"))
      (node (ref "C30") (pin "2") (pinfunction "2_2") (pintype "passive"))
      (node (ref "C31") (pin "2") (pinfunction "2_2") (pintype "passive"))
      (node (ref "C32") (pin "2") (pinfunction "2_2") (pintype "passive"))
      (node (ref "C33") (pin "2") (pinfunction "2_2") (pintype "passive"))
      (node (ref "C34") (pin "2") (pinfunction "2_2") (pintype "passive"))
      (node (ref "C35") (pin "2") (pinfunction "2_2") (pintype "passive"))
      (node (ref "C36") (pin "2") (pinfunction "2_2") (pintype "passive"))
      (node (ref "C37") (pin "2") (pinfunction "2_2") (pintype "passive"))
      (node (ref "C38") (pin "2") (pinfunction "2_2") (pintype "passive"))
      (node (ref "C39") (pin "2") (pinfunction "2_2") (pintype "passive"))
      (node (ref "C4") (pin "2") (pinfunction "2_2") (pintype "passive"))
      (node (ref "C40") (pin "2") (pinfunction "2_2") (pintype "passive"))
      (node (ref "C5") (pin "2") (pinfunction "2_2") (pintype "passive"))
      (node (ref "C6") (pin "2") (pinfunction "2_2") (pintype "passive"))
      (node (ref "C7") (pin "2") (pinfunction "2_2") (pintype "passive"))
      (node (ref "C8") (pin "2") (pinfunction "2_2") (pintype "passive"))
      (node (ref "C9") (pin "2") (pinfunction "2_2") (pintype "passive"))
      (node (ref "DISP1") (pin "1") (pinfunction "1_1") (pintype "passive"))
      (node (ref "GND") (pin "TP") (pinfunction "TP_TP") (pintype "input"))
      (node (ref "J1") (pin "EARTH") (pinfunction "EARTH_EARTH") (pintype "bidirectional"))
      (node (ref "J2") (pin "1") (pinfunction "GND_1") (pintype "passive"))
      (node (ref "J2") (pin "MT1") (pinfunction "MT_MT1") (pintype "bidirectional"))
      (node (ref "J2") (pin "MT2") (pinfunction "MT_MT2") (pintype "bidirectional"))
      (node (ref "LED1") (pin "3-GND") (pinfunction "GND_3-GND") (pintype "power_in"))
      (node (ref "LED10") (pin "3-GND") (pinfunction "GND_3-GND") (pintype "power_in"))
      (node (ref "LED11") (pin "3-GND") (pinfunction "GND_3-GND") (pintype "power_in"))
      (node (ref "LED12") (pin "3-GND") (pinfunction "GND_3-GND") (pintype "power_in"))
      (node (ref "LED13") (pin "3-GND") (pinfunction "GND_3-GND") (pintype "power_in"))
      (node (ref "LED14") (pin "3-GND") (pinfunction "GND_3-GND") (pintype "power_in"))
      (node (ref "LED15") (pin "3-GND") (pinfunction "GND_3-GND") (pintype "power_in"))
      (node (ref "LED16") (pin "3-GND") (pinfunction "GND_3-GND") (pintype "power_in"))
      (node (ref "LED17") (pin "3-GND") (pinfunction "GND_3-GND") (pintype "power_in"))
      (node (ref "LED18") (pin "3-GND") (pinfunction "GND_3-GND") (pintype "power_in"))
      (node (ref "LED19") (pin "3-GND") (pinfunction "GND_3-GND") (pintype "power_in"))
      (node (ref "LED2") (pin "3-GND") (pinfunction "GND_3-GND") (pintype "power_in"))
      (node (ref "LED20") (pin "3-GND") (pinfunction "GND_3-GND") (pintype "power_in"))
      (node (ref "LED21") (pin "3-GND") (pinfunction "GND_3-GND") (pintype "power_in"))
      (node (ref "LED22") (pin "3-GND") (pinfunction "GND_3-GND") (pintype "power_in"))
      (node (ref "LED23") (pin "3-GND") (pinfunction "GND_3-GND") (pintype "power_in"))
      (node (ref "LED24") (pin "3-GND") (pinfunction "GND_3-GND") (pintype "power_in"))
      (node (ref "LED25") (pin "3-GND") (pinfunction "GND_3-GND") (pintype "power_in"))
      (node (ref "LED26") (pin "3-GND") (pinfunction "GND_3-GND") (pintype "power_in"))
      (node (ref "LED27") (pin "3-GND") (pinfunction "GND_3-GND") (pintype "power_in"))
      (node (ref "LED28") (pin "3-GND") (pinfunction "GND_3-GND") (pintype "power_in"))
      (node (ref "LED29") (pin "3-GND") (pinfunction "GND_3-GND") (pintype "power_in"))
      (node (ref "LED3") (pin "3-GND") (pinfunction "GND_3-GND") (pintype "power_in"))
      (node (ref "LED30") (pin "3-GND") (pinfunction "GND_3-GND") (pintype "power_in"))
      (node (ref "LED31") (pin "3-GND") (pinfunction "GND_3-GND") (pintype "power_in"))
      (node (ref "LED32") (pin "3-GND") (pinfunction "GND_3-GND") (pintype "power_in"))
      (node (ref "LED33") (pin "3-GND") (pinfunction "GND_3-GND") (pintype "power_in"))
      (node (ref "LED34") (pin "3-GND") (pinfunction "GND_3-GND") (pintype "power_in"))
      (node (ref "LED35") (pin "3-GND") (pinfunction "GND_3-GND") (pintype "power_in"))
      (node (ref "LED36") (pin "3-GND") (pinfunction "GND_3-GND") (pintype "power_in"))
      (node (ref "LED37") (pin "3-GND") (pinfunction "GND_3-GND") (pintype "power_in"))
      (node (ref "LED38") (pin "3-GND") (pinfunction "GND_3-GND") (pintype "power_in"))
      (node (ref "LED39") (pin "3-GND") (pinfunction "GND_3-GND") (pintype "power_in"))
      (node (ref "LED4") (pin "3-GND") (pinfunction "GND_3-GND") (pintype "power_in"))
      (node (ref "LED40") (pin "3-GND") (pinfunction "GND_3-GND") (pintype "power_in"))
      (node (ref "LED5") (pin "3-GND") (pinfunction "GND_3-GND") (pintype "power_in"))
      (node (ref "LED6") (pin "3-GND") (pinfunction "GND_3-GND") (pintype "power_in"))
      (node (ref "LED7") (pin "3-GND") (pinfunction "GND_3-GND") (pintype "power_in"))
      (node (ref "LED8") (pin "3-GND") (pinfunction "GND_3-GND") (pintype "power_in"))
      (node (ref "LED9") (pin "3-GND") (pinfunction "GND_3-GND") (pintype "power_in"))
      (node (ref "R1") (pin "1") (pinfunction "1_1") (pintype "passive"))
      (node (ref "R10") (pin "1") (pinfunction "1_1") (pintype "passive"))
      (node (ref "R11") (pin "1") (pinfunction "1_1") (pintype "passive"))
      (node (ref "R12") (pin "1") (pinfunction "1_1") (pintype "passive"))
      (node (ref "R13") (pin "1") (pinfunction "1_1") (pintype "passive"))
      (node (ref "R14") (pin "1") (pinfunction "1_1") (pintype "passive"))
      (node (ref "R2") (pin "1") (pinfunction "1_1") (pintype "passive"))
      (node (ref "R3") (pin "1") (pinfunction "1_1") (pintype "passive"))
      (node (ref "R4") (pin "1") (pinfunction "1_1") (pintype "passive"))
      (node (ref "R5") (pin "1") (pinfunction "1_1") (pintype "passive"))
      (node (ref "R6") (pin "1") (pinfunction "1_1") (pintype "passive"))
      (node (ref "R7") (pin "1") (pinfunction "1_1") (pintype "passive"))
      (node (ref "R8") (pin "1") (pinfunction "1_1") (pintype "passive"))
      (node (ref "R9") (pin "1") (pinfunction "1_1") (pintype "passive"))
      (node (ref "U1") (pin "P$13") (pinfunction "GND_P$13") (pintype "power_in"))
      (node (ref "U1") (pin "P$18") (pinfunction "GND_P$18") (pintype "power_in"))
      (node (ref "U1") (pin "P$23") (pinfunction "GND_P$23") (pintype "power_in"))
      (node (ref "U1") (pin "P$28") (pinfunction "GND_P$28") (pintype "power_in"))
      (node (ref "U1") (pin "P$3") (pinfunction "GND_P$3") (pintype "power_in"))
      (node (ref "U1") (pin "P$33") (pinfunction "GND_P$33") (pintype "power_in"))
      (node (ref "U1") (pin "P$38") (pinfunction "GND_P$38") (pintype "power_in"))
      (node (ref "U1") (pin "P$8") (pinfunction "GND_P$8") (pintype "power_in"))
    )
    (net (code "13") (name "MIDI_OUT") (class "Default")
      (node (ref "R16") (pin "2") (pinfunction "2_2") (pintype "passive"))
      (node (ref "U1") (pin "P$26") (pinfunction "GP20_P$26") (pintype "bidirectional"))
    )
    (net (code "14") (name "NEOPIXEL") (class "Default")
      (node (ref "LED1") (pin "4-DIN") (pinfunction "DI_4-DIN") (pintype "input"))
      (node (ref "NEOPIXEL") (pin "TP") (pinfunction "TP_TP") (pintype "input"))
      (node (ref "U1") (pin "P$34") (pinfunction "GP28_P$34") (pintype "bidirectional"))
    )
    (net (code "15") (name "Net-(3VM-PadTP)") (class "Default")
      (node (ref "3VM") (pin "TP") (pinfunction "TP_TP") (pintype "input"))
      (node (ref "J1") (pin "RING1") (pinfunction "RING1_RING1") (pintype "bidirectional"))
      (node (ref "R15") (pin "1") (pinfunction "1_1") (pintype "passive"))
    )
    (net (code "16") (name "Net-(J1-PadTIP)") (class "Default")
      (node (ref "J1") (pin "TIP") (pinfunction "TIP_TIP") (pintype "bidirectional"))
      (node (ref "M") (pin "TP") (pinfunction "TP_TP") (pintype "input"))
      (node (ref "R16") (pin "1") (pinfunction "1_1") (pintype "passive"))
    )
    (net (code "17") (name "Net-(LED1-DO)") (class "Default")
      (node (ref "LED1") (pin "2-DOUT") (pinfunction "DO_2-DOUT") (pintype "output"))
      (node (ref "LED2") (pin "4-DIN") (pinfunction "DI_4-DIN") (pintype "input"))
    )
    (net (code "18") (name "Net-(LED2-DO)") (class "Default")
      (node (ref "LED2") (pin "2-DOUT") (pinfunction "DO_2-DOUT") (pintype "output"))
      (node (ref "LED3") (pin "4-DIN") (pinfunction "DI_4-DIN") (pintype "input"))
    )
    (net (code "19") (name "Net-(LED3-DO)") (class "Default")
      (node (ref "LED3") (pin "2-DOUT") (pinfunction "DO_2-DOUT") (pintype "output"))
      (node (ref "LED4") (pin "4-DIN") (pinfunction "DI_4-DIN") (pintype "input"))
    )
    (net (code "20") (name "Net-(LED4-DO)") (class "Default")
      (node (ref "LED4") (pin "2-DOUT") (pinfunction "DO_2-DOUT") (pintype "output"))
      (node (ref "LED5") (pin "4-DIN") (pinfunction "DI_4-DIN") (pintype "input"))
    )
    (net (code "21") (name "Net-(LED5-DO)") (class "Default")
      (node (ref "LED5") (pin "2-DOUT") (pinfunction "DO_2-DOUT") (pintype "output"))
      (node (ref "LED6") (pin "4-DIN") (pinfunction "DI_4-DIN") (pintype "input"))
    )
    (net (code "22") (name "Net-(LED6-DO)") (class "Default")
      (node (ref "LED6") (pin "2-DOUT") (pinfunction "DO_2-DOUT") (pintype "output"))
      (node (ref "LED7") (pin "4-DIN") (pinfunction "DI_4-DIN") (pintype "input"))
    )
    (net (code "23") (name "Net-(LED7-DO)") (class "Default")
      (node (ref "LED7") (pin "2-DOUT") (pinfunction "DO_2-DOUT") (pintype "output"))
      (node (ref "LED8") (pin "4-DIN") (pinfunction "DI_4-DIN") (pintype "input"))
    )
    (net (code "24") (name "Net-(LED8-DO)") (class "Default")
      (node (ref "LED8") (pin "2-DOUT") (pinfunction "DO_2-DOUT") (pintype "output"))
      (node (ref "LED9") (pin "4-DIN") (pinfunction "DI_4-DIN") (pintype "input"))
    )
    (net (code "25") (name "Net-(LED10-DI)") (class "Default")
      (node (ref "LED10") (pin "4-DIN") (pinfunction "DI_4-DIN") (pintype "input"))
      (node (ref "LED9") (pin "2-DOUT") (pinfunction "DO_2-DOUT") (pintype "output"))
    )
    (net (code "26") (name "Net-(LED10-DO)") (class "Default")
      (node (ref "LED10") (pin "2-DOUT") (pinfunction "DO_2-DOUT") (pintype "output"))
      (node (ref "LED11") (pin "4-DIN") (pinfunction "DI_4-DIN") (pintype "input"))
    )
    (net (code "27") (name "Net-(LED11-DO)") (class "Default")
      (node (ref "LED11") (pin "2-DOUT") (pinfunction "DO_2-DOUT") (pintype "output"))
      (node (ref "LED12") (pin "4-DIN") (pinfunction "DI_4-DIN") (pintype "input"))
    )
    (net (code "28") (name "Net-(LED12-DO)") (class "Default")
      (node (ref "LED12") (pin "2-DOUT") (pinfunction "DO_2-DOUT") (pintype "output"))
      (node (ref "LED13") (pin "4-DIN") (pinfunction "DI_4-DIN") (pintype "input"))
    )
    (net (code "29") (name "Net-(LED13-DO)") (class "Default")
      (node (ref "LED13") (pin "2-DOUT") (pinfunction "DO_2-DOUT") (pintype "output"))
      (node (ref "LED14") (pin "4-DIN") (pinfunction "DI_4-DIN") (pintype "input"))
    )
    (net (code "30") (name "Net-(LED14-DO)") (class "Default")
      (node (ref "LED14") (pin "2-DOUT") (pinfunction "DO_2-DOUT") (pintype "output"))
      (node (ref "LED15") (pin "4-DIN") (pinfunction "DI_4-DIN") (pintype "input"))
    )
    (net (code "31") (name "Net-(LED15-DO)") (class "Default")
      (node (ref "LED15") (pin "2-DOUT") (pinfunction "DO_2-DOUT") (pintype "output"))
      (node (ref "LED16") (pin "4-DIN") (pinfunction "DI_4-DIN") (pintype "input"))
    )
    (net (code "32") (name "Net-(LED16-DO)") (class "Default")
      (node (ref "LED16") (pin "2-DOUT") (pinfunction "DO_2-DOUT") (pintype "output"))
      (node (ref "LED17") (pin "4-DIN") (pinfunction "DI_4-DIN") (pintype "input"))
    )
    (net (code "33") (name "Net-(LED17-DO)") (class "Default")
      (node (ref "LED17") (pin "2-DOUT") (pinfunction "DO_2-DOUT") (pintype "output"))
      (node (ref "LED18") (pin "4-DIN") (pinfunction "DI_4-DIN") (pintype "input"))
    )
    (net (code "34") (name "Net-(LED18-DO)") (class "Default")
      (node (ref "LED18") (pin "2-DOUT") (pinfunction "DO_2-DOUT") (pintype "output"))
      (node (ref "LED19") (pin "4-DIN") (pinfunction "DI_4-DIN") (pintype "input"))
    )
    (net (code "35") (name "Net-(LED19-DO)") (class "Default")
      (node (ref "LED19") (pin "2-DOUT") (pinfunction "DO_2-DOUT") (pintype "output"))
      (node (ref "LED20") (pin "4-DIN") (pinfunction "DI_4-DIN") (pintype "input"))
    )
    (net (code "36") (name "Net-(LED20-DO)") (class "Default")
      (node (ref "LED20") (pin "2-DOUT") (pinfunction "DO_2-DOUT") (pintype "output"))
      (node (ref "LED21") (pin "4-DIN") (pinfunction "DI_4-DIN") (pintype "input"))
    )
    (net (code "37") (name "Net-(LED21-DO)") (class "Default")
      (node (ref "LED21") (pin "2-DOUT") (pinfunction "DO_2-DOUT") (pintype "output"))
      (node (ref "LED22") (pin "4-DIN") (pinfunction "DI_4-DIN") (pintype "input"))
    )
    (net (code "38") (name "Net-(LED22-DO)") (class "Default")
      (node (ref "LED22") (pin "2-DOUT") (pinfunction "DO_2-DOUT") (pintype "output"))
      (node (ref "LED23") (pin "4-DIN") (pinfunction "DI_4-DIN") (pintype "input"))
    )
    (net (code "39") (name "Net-(LED23-DO)") (class "Default")
      (node (ref "LED23") (pin "2-DOUT") (pinfunction "DO_2-DOUT") (pintype "output"))
      (node (ref "LED24") (pin "4-DIN") (pinfunction "DI_4-DIN") (pintype "input"))
    )
    (net (code "40") (name "Net-(LED24-DO)") (class "Default")
      (node (ref "LED24") (pin "2-DOUT") (pinfunction "DO_2-DOUT") (pintype "output"))
      (node (ref "LED25") (pin "4-DIN") (pinfunction "DI_4-DIN") (pintype "input"))
    )
    (net (code "41") (name "Net-(LED25-DO)") (class "Default")
      (node (ref "LED25") (pin "2-DOUT") (pinfunction "DO_2-DOUT") (pintype "output"))
      (node (ref "LED26") (pin "4-DIN") (pinfunction "DI_4-DIN") (pintype "input"))
    )
    (net (code "42") (name "Net-(LED26-DO)") (class "Default")
      (node (ref "LED26") (pin "2-DOUT") (pinfunction "DO_2-DOUT") (pintype "output"))
      (node (ref "LED27") (pin "4-DIN") (pinfunction "DI_4-DIN") (pintype "input"))
    )
    (net (code "43") (name "Net-(LED27-DO)") (class "Default")
      (node (ref "LED27") (pin "2-DOUT") (pinfunction "DO_2-DOUT") (pintype "output"))
      (node (ref "LED28") (pin "4-DIN") (pinfunction "DI_4-DIN") (pintype "input"))
    )
    (net (code "44") (name "Net-(LED28-DO)") (class "Default")
      (node (ref "LED28") (pin "2-DOUT") (pinfunction "DO_2-DOUT") (pintype "output"))
      (node (ref "LED29") (pin "4-DIN") (pinfunction "DI_4-DIN") (pintype "input"))
    )
    (net (code "45") (name "Net-(LED29-DO)") (class "Default")
      (node (ref "LED29") (pin "2-DOUT") (pinfunction "DO_2-DOUT") (pintype "output"))
      (node (ref "LED30") (pin "4-DIN") (pinfunction "DI_4-DIN") (pintype "input"))
    )
    (net (code "46") (name "Net-(LED30-DO)") (class "Default")
      (node (ref "LED30") (pin "2-DOUT") (pinfunction "DO_2-DOUT") (pintype "output"))
      (node (ref "LED31") (pin "4-DIN") (pinfunction "DI_4-DIN") (pintype "input"))
    )
    (net (code "47") (name "Net-(LED31-DO)") (class "Default")
      (node (ref "LED31") (pin "2-DOUT") (pinfunction "DO_2-DOUT") (pintype "output"))
      (node (ref "LED32") (pin "4-DIN") (pinfunction "DI_4-DIN") (pintype "input"))
    )
    (net (code "48") (name "Net-(LED32-DO)") (class "Default")
      (node (ref "LED32") (pin "2-DOUT") (pinfunction "DO_2-DOUT") (pintype "output"))
      (node (ref "LED33") (pin "4-DIN") (pinfunction "DI_4-DIN") (pintype "input"))
    )
    (net (code "49") (name "Net-(LED33-DO)") (class "Default")
      (node (ref "LED33") (pin "2-DOUT") (pinfunction "DO_2-DOUT") (pintype "output"))
      (node (ref "LED34") (pin "4-DIN") (pinfunction "DI_4-DIN") (pintype "input"))
    )
    (net (code "50") (name "Net-(LED34-DO)") (class "Default")
      (node (ref "LED34") (pin "2-DOUT") (pinfunction "DO_2-DOUT") (pintype "output"))
      (node (ref "LED35") (pin "4-DIN") (pinfunction "DI_4-DIN") (pintype "input"))
    )
    (net (code "51") (name "Net-(LED35-DO)") (class "Default")
      (node (ref "LED35") (pin "2-DOUT") (pinfunction "DO_2-DOUT") (pintype "output"))
      (node (ref "LED36") (pin "4-DIN") (pinfunction "DI_4-DIN") (pintype "input"))
    )
    (net (code "52") (name "Net-(LED36-DO)") (class "Default")
      (node (ref "LED36") (pin "2-DOUT") (pinfunction "DO_2-DOUT") (pintype "output"))
      (node (ref "LED37") (pin "4-DIN") (pinfunction "DI_4-DIN") (pintype "input"))
    )
    (net (code "53") (name "Net-(LED37-DO)") (class "Default")
      (node (ref "LED37") (pin "2-DOUT") (pinfunction "DO_2-DOUT") (pintype "output"))
      (node (ref "LED38") (pin "4-DIN") (pinfunction "DI_4-DIN") (pintype "input"))
    )
    (net (code "54") (name "Net-(LED38-DO)") (class "Default")
      (node (ref "LED38") (pin "2-DOUT") (pinfunction "DO_2-DOUT") (pintype "output"))
      (node (ref "LED39") (pin "4-DIN") (pinfunction "DI_4-DIN") (pintype "input"))
    )
    (net (code "55") (name "Net-(LED39-DO)") (class "Default")
      (node (ref "LED39") (pin "2-DOUT") (pinfunction "DO_2-DOUT") (pintype "output"))
      (node (ref "LED40") (pin "4-DIN") (pinfunction "DI_4-DIN") (pintype "input"))
    )
    (net (code "56") (name "Net-(U1-GP16)") (class "Default")
      (node (ref "16") (pin "TP") (pinfunction "TP_TP") (pintype "input"))
      (node (ref "U1") (pin "P$21") (pinfunction "GP16_P$21") (pintype "bidirectional"))
    )
    (net (code "57") (name "Net-(U1-GP17)") (class "Default")
      (node (ref "17") (pin "TP") (pinfunction "TP_TP") (pintype "input"))
      (node (ref "U1") (pin "P$22") (pinfunction "GP17_P$22") (pintype "bidirectional"))
    )
    (net (code "58") (name "Net-(U1-GP18)") (class "Default")
      (node (ref "18") (pin "TP") (pinfunction "TP_TP") (pintype "input"))
      (node (ref "U1") (pin "P$24") (pinfunction "GP18_P$24") (pintype "bidirectional"))
    )
    (net (code "59") (name "Net-(U1-GP19)") (class "Default")
      (node (ref "19") (pin "TP") (pinfunction "TP_TP") (pintype "input"))
      (node (ref "U1") (pin "P$25") (pinfunction "GP19_P$25") (pintype "bidirectional"))
    )
    (net (code "60") (name "ROW1") (class "Default")
      (node (ref "K1") (pin "T2") (pinfunction "T2_T2") (pintype "bidirectional"))
      (node (ref "K10") (pin "T2") (pinfunction "T2_T2") (pintype "bidirectional"))
      (node (ref "K2") (pin "T2") (pinfunction "T2_T2") (pintype "bidirectional"))
      (node (ref "K3") (pin "T2") (pinfunction "T2_T2") (pintype "bidirectional"))
      (node (ref "K4") (pin "T2") (pinfunction "T2_T2") (pintype "bidirectional"))
      (node (ref "K5") (pin "T2") (pinfunction "T2_T2") (pintype "bidirectional"))
      (node (ref "K6") (pin "T2") (pinfunction "T2_T2") (pintype "bidirectional"))
      (node (ref "K7") (pin "T2") (pinfunction "T2_T2") (pintype "bidirectional"))
      (node (ref "K8") (pin "T2") (pinfunction "T2_T2") (pintype "bidirectional"))
      (node (ref "K9") (pin "T2") (pinfunction "T2_T2") (pintype "bidirectional"))
      (node (ref "R11") (pin "2") (pinfunction "2_2") (pintype "passive"))
      (node (ref "U1") (pin "P$14") (pinfunction "GP10_P$14") (pintype "bidirectional"))
    )
    (net (code "61") (name "ROW2") (class "Default")
      (node (ref "K11") (pin "T2") (pinfunction "T2_T2") (pintype "bidirectional"))
      (node (ref "K12") (pin "T2") (pinfunction "T2_T2") (pintype "bidirectional"))
      (node (ref "K13") (pin "T2") (pinfunction "T2_T2") (pintype "bidirectional"))
      (node (ref "K14") (pin "T2") (pinfunction "T2_T2") (pintype "bidirectional"))
      (node (ref "K15") (pin "T2") (pinfunction "T2_T2") (pintype "bidirectional"))
      (node (ref "K16") (pin "T2") (pinfunction "T2_T2") (pintype "bidirectional"))
      (node (ref "K17") (pin "T2") (pinfunction "T2_T2") (pintype "bidirectional"))
      (node (ref "K18") (pin "T2") (pinfunction "T2_T2") (pintype "bidirectional"))
      (node (ref "K19") (pin "T2") (pinfunction "T2_T2") (pintype "bidirectional"))
      (node (ref "K20") (pin "T2") (pinfunction "T2_T2") (pintype "bidirectional"))
      (node (ref "R12") (pin "2") (pinfunction "2_2") (pintype "passive"))
      (node (ref "U1") (pin "P$15") (pinfunction "GP11_P$15") (pintype "bidirectional"))
    )
    (net (code "62") (name "ROW3") (class "Default")
      (node (ref "K21") (pin "T2") (pinfunction "T2_T2") (pintype "bidirectional"))
      (node (ref "K22") (pin "T2") (pinfunction "T2_T2") (pintype "bidirectional"))
      (node (ref "K23") (pin "T2") (pinfunction "T2_T2") (pintype "bidirectional"))
      (node (ref "K24") (pin "T2") (pinfunction "T2_T2") (pintype "bidirectional"))
      (node (ref "K25") (pin "T2") (pinfunction "T2_T2") (pintype "bidirectional"))
      (node (ref "K26") (pin "T2") (pinfunction "T2_T2") (pintype "bidirectional"))
      (node (ref "K27") (pin "T2") (pinfunction "T2_T2") (pintype "bidirectional"))
      (node (ref "K28") (pin "T2") (pinfunction "T2_T2") (pintype "bidirectional"))
      (node (ref "K29") (pin "T2") (pinfunction "T2_T2") (pintype "bidirectional"))
      (node (ref "K30") (pin "T2") (pinfunction "T2_T2") (pintype "bidirectional"))
      (node (ref "R13") (pin "2") (pinfunction "2_2") (pintype "passive"))
      (node (ref "U1") (pin "P$16") (pinfunction "GP12_P$16") (pintype "bidirectional"))
    )
    (net (code "63") (name "ROW4") (class "Default")
      (node (ref "K31") (pin "T2") (pinfunction "T2_T2") (pintype "bidirectional"))
      (node (ref "K32") (pin "T2") (pinfunction "T2_T2") (pintype "bidirectional"))
      (node (ref "K33") (pin "T2") (pinfunction "T2_T2") (pintype "bidirectional"))
      (node (ref "K34") (pin "T2") (pinfunction "T2_T2") (pintype "bidirectional"))
      (node (ref "K35") (pin "T2") (pinfunction "T2_T2") (pintype "bidirectional"))
      (node (ref "K36") (pin "T2") (pinfunction "T2_T2") (pintype "bidirectional"))
      (node (ref "K37") (pin "T2") (pinfunction "T2_T2") (pintype "bidirectional"))
      (node (ref "K38") (pin "T2") (pinfunction "T2_T2") (pintype "bidirectional"))
      (node (ref "K39") (pin "T2") (pinfunction "T2_T2") (pintype "bidirectional"))
      (node (ref "K40") (pin "T2") (pinfunction "T2_T2") (pintype "bidirectional"))
      (node (ref "R14") (pin "2") (pinfunction "2_2") (pintype "passive"))
      (node (ref "U1") (pin "P$17") (pinfunction "GP13_P$17") (pintype "bidirectional"))
    )
    (net (code "64") (name "SCL") (class "Default")
      (node (ref "DISP1") (pin "3") (pinfunction "3_3") (pintype "passive"))
      (node (ref "J2") (pin "4") (pinfunction "SCL_4") (pintype "passive"))
      (node (ref "U1") (pin "P$20") (pinfunction "GP15_P$20") (pintype "bidirectional"))
    )
    (net (code "65") (name "SDA") (class "Default")
      (node (ref "DISP1") (pin "4") (pinfunction "4_4") (pintype "passive"))
      (node (ref "J2") (pin "3") (pinfunction "SDA_3") (pintype "passive"))
      (node (ref "U1") (pin "P$19") (pinfunction "GP14_P$19") (pintype "bidirectional"))
    )
    (net (code "66") (name "SWGND") (class "Default")
      (node (ref "U1") (pin "P$42") (pinfunction "SWGND_P$42") (pintype "power_in"))
    )
    (net (code "67") (name "VBUS") (class "Default")
      (node (ref "U1") (pin "P$40") (pinfunction "VBUS_P$40") (pintype "power_in"))
    )
    (net (code "68") (name "VSYS") (class "Default")
      (node (ref "U1") (pin "P$39") (pinfunction "VSYS_P$39") (pintype "power_in"))
    )
    (net (code "69") (name "unconnected-(J1-PadRING2)") (class "Default")
      (node (ref "J1") (pin "RING2") (pinfunction "RING2_RING2") (pintype "bidirectional"))
    )
    (net (code "70") (name "unconnected-(LED40-DO-Pad2-DOUT)") (class "Default")
      (node (ref "LED40") (pin "2-DOUT") (pinfunction "DO_2-DOUT") (pintype "output"))
    )
    (net (code "71") (name "unconnected-(U1-3V3_EN-PadP$37)") (class "Default")
      (node (ref "U1") (pin "P$37") (pinfunction "3V3_EN_P$37") (pintype "input"))
    )
    (net (code "72") (name "unconnected-(U1-ADC_REF-PadP$35)") (class "Default")
      (node (ref "U1") (pin "P$35") (pinfunction "ADC_REF_P$35") (pintype "input"))
    )
    (net (code "73") (name "unconnected-(U1-GP21-PadP$27)") (class "Default")
      (node (ref "U1") (pin "P$27") (pinfunction "GP21_P$27") (pintype "bidirectional"))
    )
    (net (code "74") (name "unconnected-(U1-GP22-PadP$29)") (class "Default")
      (node (ref "U1") (pin "P$29") (pinfunction "GP22_P$29") (pintype "bidirectional"))
    )
    (net (code "75") (name "unconnected-(U1-GP26-PadP$31)") (class "Default")
      (node (ref "U1") (pin "P$31") (pinfunction "GP26_P$31") (pintype "bidirectional"))
    )
    (net (code "76") (name "unconnected-(U1-GP27-PadP$32)") (class "Default")
      (node (ref "U1") (pin "P$32") (pinfunction "GP27_P$32") (pintype "bidirectional"))
    )
    (net (code "77") (name "unconnected-(U1-RUN-PadP$30)") (class "Default")
      (node (ref "U1") (pin "P$30") (pinfunction "RUN_P$30") (pintype "input"))
    )
    (net (code "78") (name "unconnected-(U1-SWCLK-PadP$41)") (class "Default")
      (node (ref "U1") (pin "P$41") (pinfunction "SWCLK_P$41") (pintype "input"))
    )
    (net (code "79") (name "unconnected-(U1-SWDIO-PadP$43)") (class "Default")
      (node (ref "U1") (pin "P$43") (pinfunction "SWDIO_P$43") (pintype "bidirectional"))
    )
  )
)
